# SENSORS.net
KiCad netlist of a schematic drawn in Altium Designer
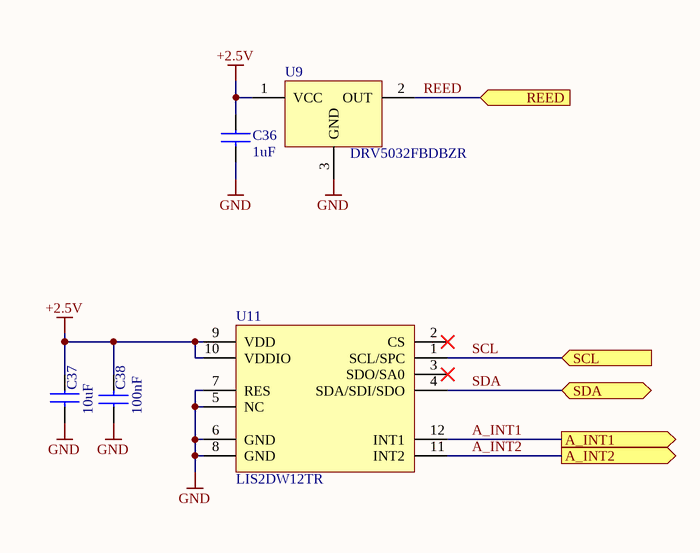
[diagram p0: SENSORS.SchDoc]

(export (version "E")
  (design (tool "Eeschema 10.0.6"))
  (components
    (comp (ref "C36")
      (value "1uF")
      (footprint "CAP0402")
      (description "CAP CER 1UF 10V 20% X5R 0402")
      (fields
        (field (name "MANUFACTURER") "Murata")
        (field (name "MANUFACTURER PART NUMBER") "GRM155R61A105ME15D")
      )
      (libsource (lib "Passive") (part "C - 1uF/0402"))
    )
    (comp (ref "C37")
      (value "10uF")
      (footprint "CAP0603")
      (description "Cap Ceramic 10uF 10V X5R 10% SMD 0603 85C Paper T/R")
      (fields
        (field (name "MANUFACTURER") "Samsung")
        (field (name "MANUFACTURER PART NUMBER") "CL10A106KP8NNNC")
      )
      (libsource (lib "Passive") (part "C - 10uF/10V"))
    )
    (comp (ref "C38")
      (value "100nF")
      (footprint "CAP0402")
      (fields
        (field (name "MANUFACTURER") "Multicomp")
        (field (name "MANUFACTURER PART NUMBER") "MC0402X104J160CT")
        (field (name "TOLERANCE") "5%")
      )
      (libsource (lib "Passive") (part "C - 100nF/0402"))
    )
    (comp (ref "U9")
      (value "DRV5032FBDBZR")
      (footprint "SOT23-3AL")
      (description "Board Mount Hall Effect/Magnetic Sensors LP HALL 32FBDBZR")
      (fields
        (field (name "MANUFACTURER") "TDK InvenSense")
        (field (name "MANUFACTURER PART NUMBER") "MPU-9250")
      )
      (libsource (lib "Active") (part "SEN - DRV5032FBDBZR"))
    )
    (comp (ref "U11")
      (value "LIS2DW12TR")
      (footprint "LGA-12")
      (description "MEMS Accelerometer, Digital, X, Y, Z, ± 2g, ± 4g, ± 8g, ± 16g, 1.62 V, 3.6 V")
      (fields
        (field (name "MANUFACTURER") "TDK InvenSense")
        (field (name "MANUFACTURER PART NUMBER") "MPU-9250")
      )
      (libsource (lib "Active") (part "SEN - LIS2DW12TR"))
    )
  )
  (nets
    (net (code "1") (name "+2.5V") (class "Default")
      (node (ref "C36") (pin "1") (pinfunction "1_1") (pintype "passive"))
      (node (ref "C37") (pin "1") (pinfunction "1_1") (pintype "passive"))
      (node (ref "C38") (pin "2") (pinfunction "2_2") (pintype "passive"))
      (node (ref "U11") (pin "10") (pinfunction "VDDIO_10") (pintype "passive"))
      (node (ref "U11") (pin "9") (pinfunction "VDD_9") (pintype "passive"))
      (node (ref "U9") (pin "1") (pinfunction "VCC_1") (pintype "passive"))
    )
    (net (code "2") (name "/A_INT1") (class "Default")
      (node (ref "U11") (pin "12") (pinfunction "INT1_12") (pintype "passive"))
    )
    (net (code "3") (name "/A_INT2") (class "Default")
      (node (ref "U11") (pin "11") (pinfunction "INT2_11") (pintype "passive"))
    )
    (net (code "4") (name "/REED") (class "Default")
      (node (ref "U9") (pin "2") (pinfunction "OUT_2") (pintype "passive"))
    )
    (net (code "5") (name "/SCL") (class "Default")
      (node (ref "U11") (pin "1") (pinfunction "SCL/SPC_1") (pintype "passive"))
    )
    (net (code "6") (name "/SDA") (class "Default")
      (node (ref "U11") (pin "4") (pinfunction "SDA/SDI/SDO_4") (pintype "passive"))
    )
    (net (code "7") (name "GND") (class "Default")
      (node (ref "C36") (pin "2") (pinfunction "2_2") (pintype "passive"))
      (node (ref "C37") (pin "2") (pinfunction "2_2") (pintype "passive"))
      (node (ref "C38") (pin "1") (pinfunction "1_1") (pintype "passive"))
      (node (ref "U11") (pin "5") (pinfunction "NC_5") (pintype "passive"))
      (node (ref "U11") (pin "6") (pinfunction "GND_6") (pintype "passive"))
      (node (ref "U11") (pin "7") (pinfunction "RES_7") (pintype "passive"))
      (node (ref "U11") (pin "8") (pinfunction "GND_8") (pintype "passive"))
      (node (ref "U9") (pin "3") (pinfunction "GND_3") (pintype "passive"))
    )
    (net (code "8") (name "unconnected-(U11-CS-Pad2)") (class "Default")
      (node (ref "U11") (pin "2") (pinfunction "CS_2") (pintype "passive+no_connect"))
    )
    (net (code "9") (name "unconnected-(U11-SDO{slash}SA0-Pad3)") (class "Default")
      (node (ref "U11") (pin "3") (pinfunction "SDO/SA0_3") (pintype "passive+no_connect"))
    )
  )
)
